# LED_board.net
KiCad netlist of a schematic drawn in EAGLE
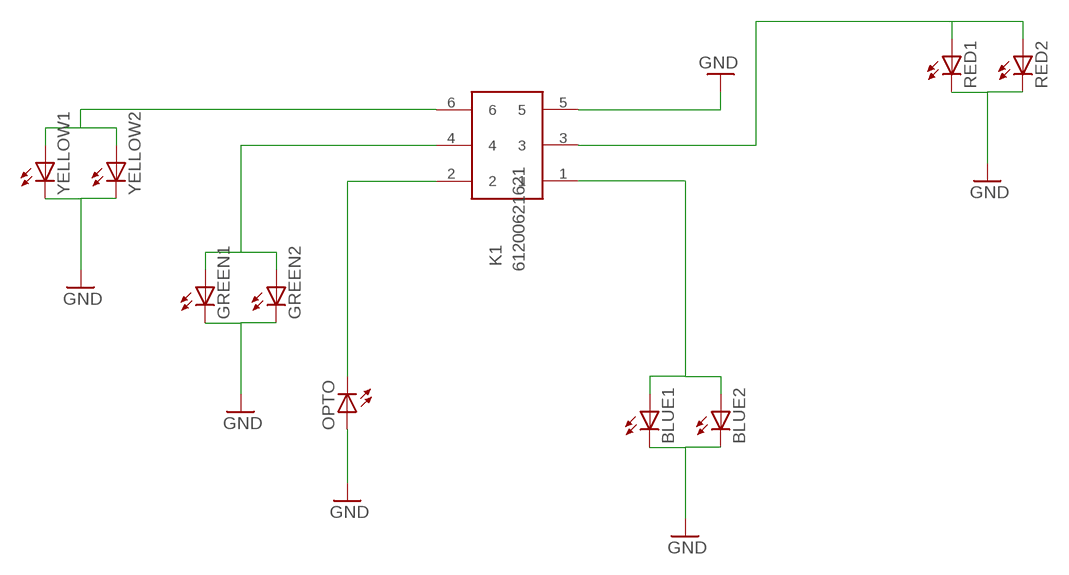
[diagram p0: schematic, sheet 1]

(export (version "E")
  (design (tool "Eeschema 10.0.6"))
  (components
    (comp (ref "BLUE1")
      (value "LED5MM")
      (footprint "eagle-import:LED5MM")
      (libsource (lib "eagle-import") (part "LED5MM"))
    )
    (comp (ref "BLUE2")
      (value "LED5MM")
      (footprint "eagle-import:LED5MM")
      (libsource (lib "eagle-import") (part "LED5MM"))
    )
    (comp (ref "GREEN1")
      (value "LED5MM")
      (footprint "eagle-import:LED5MM")
      (libsource (lib "eagle-import") (part "LED5MM"))
    )
    (comp (ref "GREEN2")
      (value "LED5MM")
      (footprint "eagle-import:LED5MM")
      (libsource (lib "eagle-import") (part "LED5MM"))
    )
    (comp (ref "K1")
      (value "61200621621")
      (footprint "eagle-import:61200621621")
      (libsource (lib "eagle-import") (part "61200621621"))
    )
    (comp (ref "OPTO")
      (value "LED5MM")
      (footprint "eagle-import:LED5MM")
      (libsource (lib "eagle-import") (part "LED5MM"))
    )
    (comp (ref "RED1")
      (value "LED5MM")
      (footprint "eagle-import:LED5MM")
      (libsource (lib "eagle-import") (part "LED5MM"))
    )
    (comp (ref "RED2")
      (value "LED5MM")
      (footprint "eagle-import:LED5MM")
      (libsource (lib "eagle-import") (part "LED5MM"))
    )
    (comp (ref "YELLOW1")
      (value "LED5MM")
      (footprint "eagle-import:LED5MM")
      (libsource (lib "eagle-import") (part "LED5MM"))
    )
    (comp (ref "YELLOW2")
      (value "LED5MM")
      (footprint "eagle-import:LED5MM")
      (libsource (lib "eagle-import") (part "LED5MM"))
    )
  )
  (nets
    (net (code "1") (name "GND") (class "Default")
      (node (ref "BLUE1") (pin "K") (pinfunction "C_K") (pintype "passive"))
      (node (ref "BLUE2") (pin "K") (pinfunction "C_K") (pintype "passive"))
      (node (ref "GREEN1") (pin "K") (pinfunction "C_K") (pintype "passive"))
      (node (ref "GREEN2") (pin "K") (pinfunction "C_K") (pintype "passive"))
      (node (ref "K1") (pin "5") (pinfunction "5_5") (pintype "passive"))
      (node (ref "OPTO") (pin "A") (pinfunction "A_A") (pintype "passive"))
      (node (ref "RED1") (pin "K") (pinfunction "C_K") (pintype "passive"))
      (node (ref "RED2") (pin "K") (pinfunction "C_K") (pintype "passive"))
      (node (ref "YELLOW1") (pin "K") (pinfunction "C_K") (pintype "passive"))
      (node (ref "YELLOW2") (pin "K") (pinfunction "C_K") (pintype "passive"))
    )
    (net (code "2") (name "Net-(BLUE1-PadA)") (class "Default")
      (node (ref "BLUE1") (pin "A") (pinfunction "A_A") (pintype "passive"))
      (node (ref "BLUE2") (pin "A") (pinfunction "A_A") (pintype "passive"))
      (node (ref "K1") (pin "1") (pinfunction "1_1") (pintype "passive"))
    )
    (net (code "3") (name "Net-(GREEN1-PadA)") (class "Default")
      (node (ref "GREEN1") (pin "A") (pinfunction "A_A") (pintype "passive"))
      (node (ref "GREEN2") (pin "A") (pinfunction "A_A") (pintype "passive"))
      (node (ref "K1") (pin "4") (pinfunction "4_4") (pintype "passive"))
    )
    (net (code "4") (name "Net-(K1-Pad3)") (class "Default")
      (node (ref "K1") (pin "3") (pinfunction "3_3") (pintype "passive"))
      (node (ref "RED1") (pin "A") (pinfunction "A_A") (pintype "passive"))
      (node (ref "RED2") (pin "A") (pinfunction "A_A") (pintype "passive"))
    )
    (net (code "5") (name "Net-(K1-Pad6)") (class "Default")
      (node (ref "K1") (pin "6") (pinfunction "6_6") (pintype "passive"))
      (node (ref "YELLOW1") (pin "A") (pinfunction "A_A") (pintype "passive"))
      (node (ref "YELLOW2") (pin "A") (pinfunction "A_A") (pintype "passive"))
    )
    (net (code "6") (name "Net-(OPTO-C)") (class "Default")
      (node (ref "K1") (pin "2") (pinfunction "2_2") (pintype "passive"))
      (node (ref "OPTO") (pin "K") (pinfunction "C_K") (pintype "passive"))
    )
  )
)
